# v5m.net
KiCad netlist of a schematic drawn in EAGLE
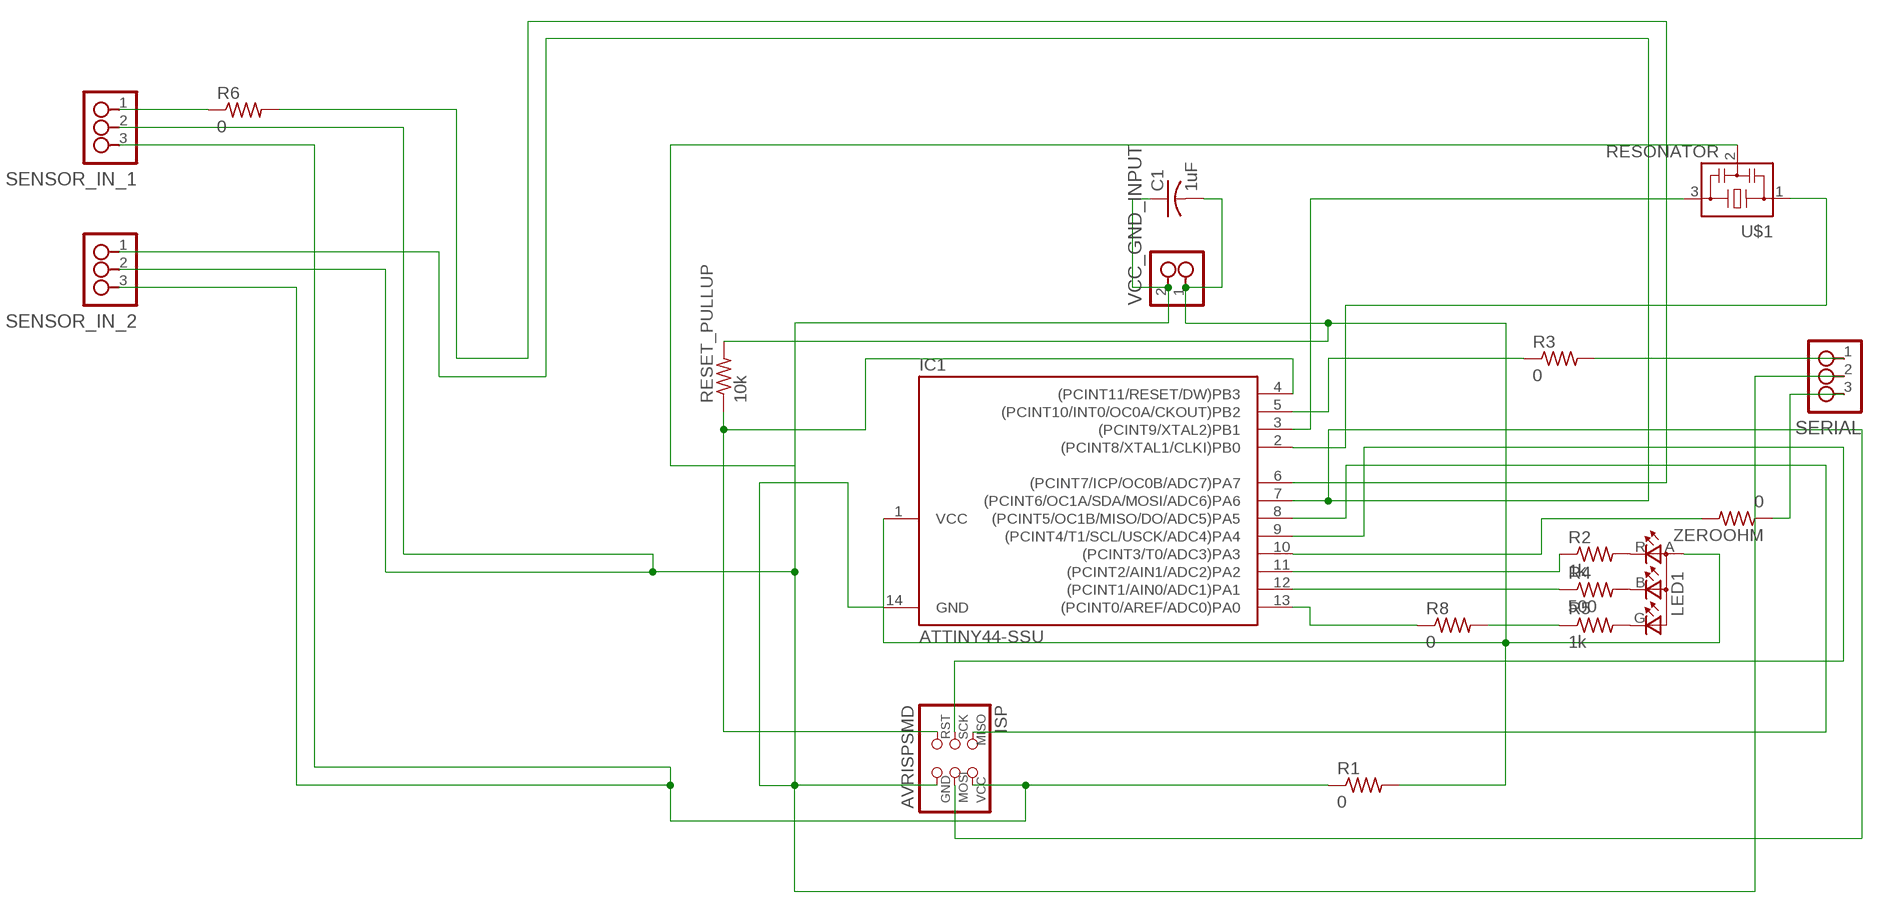
[diagram p0: schematic, sheet 1]

(export (version "E")
  (design (tool "Eeschema 10.0.6"))
  (components
    (comp (ref "C1")
      (value "1uF")
      (footprint "eagle-import:C1206")
      (libsource (lib "eagle-import") (part "C-USC1206"))
    )
    (comp (ref "IC1")
      (value "ATTINY44-SSU")
      (footprint "eagle-import:SOIC14")
      (libsource (lib "eagle-import") (part "ATTINY44-SSU"))
    )
    (comp (ref "ISP")
      (value "AVRISPSMD")
      (footprint "eagle-import:2X03SMD")
      (libsource (lib "eagle-import") (part "AVRISPSMD"))
    )
    (comp (ref "LED1")
      (value "LEDRGBOLD")
      (footprint "eagle-import:P-LCC-4-3")
      (libsource (lib "eagle-import") (part "LEDRGBOLD"))
    )
    (comp (ref "R1")
      (value "0")
      (footprint "eagle-import:R1206")
      (libsource (lib "eagle-import") (part "RES-US1206"))
    )
    (comp (ref "R2")
      (value "1k")
      (footprint "eagle-import:R1206")
      (libsource (lib "eagle-import") (part "RES-US1206"))
    )
    (comp (ref "R3")
      (value "0")
      (footprint "eagle-import:R1206")
      (libsource (lib "eagle-import") (part "RES-US1206"))
    )
    (comp (ref "R4")
      (value "500")
      (footprint "eagle-import:R1206")
      (libsource (lib "eagle-import") (part "RES-US1206"))
    )
    (comp (ref "R5")
      (value "1k")
      (footprint "eagle-import:R1206")
      (libsource (lib "eagle-import") (part "RES-US1206"))
    )
    (comp (ref "R6")
      (value "0")
      (footprint "eagle-import:R1206")
      (libsource (lib "eagle-import") (part "RES-US1206"))
    )
    (comp (ref "R8")
      (value "0")
      (footprint "eagle-import:R1206")
      (libsource (lib "eagle-import") (part "RES-US1206"))
    )
    (comp (ref "RESET_PULLUP")
      (value "10k")
      (footprint "eagle-import:R1206")
      (libsource (lib "eagle-import") (part "R-US_R1206"))
    )
    (comp (ref "SENSOR_IN_1")
      (value "3_PIN_HEADERHEADER")
      (footprint "eagle-import:SMT_PINS_3")
      (libsource (lib "eagle-import") (part "3_PIN_HEADERHEADER"))
    )
    (comp (ref "SENSOR_IN_2")
      (value "3_PIN_HEADERHEADER")
      (footprint "eagle-import:SMT_PINS_3")
      (libsource (lib "eagle-import") (part "3_PIN_HEADERHEADER"))
    )
    (comp (ref "SERIAL")
      (value "3_PIN_HEADERHEADER")
      (footprint "eagle-import:SMT_PINS_3")
      (libsource (lib "eagle-import") (part "3_PIN_HEADERHEADER"))
    )
    (comp (ref "U$1")
      (value "RESONATOR")
      (footprint "eagle-import:EFOBM")
      (libsource (lib "eagle-import") (part "RESONATOR"))
    )
    (comp (ref "VCC_GND_INPUT")
      (value "2_PIN_HEADERHEADER")
      (footprint "eagle-import:SMT_PINS_2")
      (libsource (lib "eagle-import") (part "2_PIN_HEADERHEADER"))
    )
    (comp (ref "ZEROOHM")
      (value "0")
      (footprint "eagle-import:R1206")
      (libsource (lib "eagle-import") (part "R-US_R1206"))
    )
  )
  (nets
    (net (code "1") (name "Net-(IC1-(PCINT0{slash}AREF{slash}ADC0)PA0)") (class "Default")
      (node (ref "IC1") (pin "13") (pinfunction "(PCINT0/AREF/ADC0)PA0_13") (pintype "bidirectional"))
      (node (ref "R8") (pin "1") (pinfunction "1_1") (pintype "passive"))
    )
    (net (code "2") (name "Net-(IC1-(PCINT1{slash}AIN0{slash}ADC1)PA1)") (class "Default")
      (node (ref "IC1") (pin "12") (pinfunction "(PCINT1/AIN0/ADC1)PA1_12") (pintype "bidirectional"))
      (node (ref "R4") (pin "1") (pinfunction "1_1") (pintype "passive"))
    )
    (net (code "3") (name "Net-(IC1-(PCINT2{slash}AIN1{slash}ADC2)PA2)") (class "Default")
      (node (ref "IC1") (pin "11") (pinfunction "(PCINT2/AIN1/ADC2)PA2_11") (pintype "bidirectional"))
      (node (ref "R2") (pin "1") (pinfunction "1_1") (pintype "passive"))
    )
    (net (code "4") (name "Net-(IC1-(PCINT3{slash}T0{slash}ADC3)PA3)") (class "Default")
      (node (ref "IC1") (pin "10") (pinfunction "(PCINT3/T0/ADC3)PA3_10") (pintype "bidirectional"))
      (node (ref "ZEROOHM") (pin "2") (pinfunction "2_2") (pintype "passive"))
    )
    (net (code "5") (name "Net-(IC1-(PCINT4{slash}T1{slash}SCL{slash}USCK{slash}ADC4)PA4)") (class "Default")
      (node (ref "IC1") (pin "9") (pinfunction "(PCINT4/T1/SCL/USCK/ADC4)PA4_9") (pintype "bidirectional"))
      (node (ref "ISP") (pin "3") (pinfunction "SCK_3") (pintype "passive"))
    )
    (net (code "6") (name "Net-(IC1-(PCINT5{slash}OC1B{slash}MISO{slash}DO{slash}ADC5)PA5)") (class "Default")
      (node (ref "IC1") (pin "8") (pinfunction "(PCINT5/OC1B/MISO/DO/ADC5)PA5_8") (pintype "bidirectional"))
      (node (ref "ISP") (pin "1") (pinfunction "MISO_1") (pintype "passive"))
    )
    (net (code "7") (name "Net-(IC1-(PCINT6{slash}OC1A{slash}SDA{slash}MOSI{slash}ADC6)PA6)") (class "Default")
      (node (ref "IC1") (pin "7") (pinfunction "(PCINT6/OC1A/SDA/MOSI/ADC6)PA6_7") (pintype "bidirectional"))
      (node (ref "ISP") (pin "4") (pinfunction "MOSI_4") (pintype "passive"))
      (node (ref "SENSOR_IN_2") (pin "1") (pinfunction "P$1_1") (pintype "bidirectional"))
    )
    (net (code "8") (name "Net-(IC1-(PCINT7{slash}ICP{slash}OC0B{slash}ADC7)PA7)") (class "Default")
      (node (ref "IC1") (pin "6") (pinfunction "(PCINT7/ICP/OC0B/ADC7)PA7_6") (pintype "bidirectional"))
      (node (ref "R6") (pin "2") (pinfunction "2_2") (pintype "passive"))
    )
    (net (code "9") (name "Net-(IC1-(PCINT8{slash}XTAL1{slash}CLKI)PB0)") (class "Default")
      (node (ref "IC1") (pin "2") (pinfunction "(PCINT8/XTAL1/CLKI)PB0_2") (pintype "bidirectional"))
      (node (ref "U$1") (pin "1") (pinfunction "1_1") (pintype "passive"))
    )
    (net (code "10") (name "Net-(IC1-(PCINT9{slash}XTAL2)PB1)") (class "Default")
      (node (ref "IC1") (pin "3") (pinfunction "(PCINT9/XTAL2)PB1_3") (pintype "bidirectional"))
      (node (ref "U$1") (pin "3") (pinfunction "3_3") (pintype "passive"))
    )
    (net (code "11") (name "Net-(IC1-(PCINT10{slash}INT0{slash}OC0A{slash}CKOUT)PB2)") (class "Default")
      (node (ref "IC1") (pin "5") (pinfunction "(PCINT10/INT0/OC0A/CKOUT)PB2_5") (pintype "bidirectional"))
      (node (ref "R3") (pin "1") (pinfunction "1_1") (pintype "passive"))
    )
    (net (code "12") (name "Net-(IC1-(PCINT11{slash}RESET{slash}DW)PB3)") (class "Default")
      (node (ref "IC1") (pin "4") (pinfunction "(PCINT11/RESET/DW)PB3_4") (pintype "bidirectional"))
      (node (ref "ISP") (pin "5") (pinfunction "RST_5") (pintype "passive"))
      (node (ref "RESET_PULLUP") (pin "1") (pinfunction "1_1") (pintype "passive"))
    )
    (net (code "13") (name "Net-(IC1-GND)") (class "Default")
      (node (ref "C1") (pin "1") (pinfunction "1_1") (pintype "passive"))
      (node (ref "IC1") (pin "14") (pinfunction "GND_14") (pintype "power_in"))
      (node (ref "ISP") (pin "6") (pinfunction "GND_6") (pintype "passive"))
      (node (ref "SENSOR_IN_1") (pin "2") (pinfunction "P$2_2") (pintype "bidirectional"))
      (node (ref "SENSOR_IN_2") (pin "2") (pinfunction "P$2_2") (pintype "bidirectional"))
      (node (ref "SERIAL") (pin "2") (pinfunction "P$2_2") (pintype "bidirectional"))
      (node (ref "U$1") (pin "2") (pinfunction "2_2") (pintype "passive"))
      (node (ref "VCC_GND_INPUT") (pin "2") (pinfunction "2_2") (pintype "bidirectional"))
    )
    (net (code "14") (name "Net-(IC1-VCC)") (class "Default")
      (node (ref "C1") (pin "2") (pinfunction "2_2") (pintype "passive"))
      (node (ref "IC1") (pin "1") (pinfunction "VCC_1") (pintype "power_in"))
      (node (ref "LED1") (pin "A") (pinfunction "A2_A") (pintype "passive"))
      (node (ref "R1") (pin "2") (pinfunction "2_2") (pintype "passive"))
      (node (ref "RESET_PULLUP") (pin "2") (pinfunction "2_2") (pintype "passive"))
      (node (ref "VCC_GND_INPUT") (pin "1") (pinfunction "1_1") (pintype "bidirectional"))
    )
    (net (code "15") (name "Net-(ISP-VCC)") (class "Default")
      (node (ref "ISP") (pin "2") (pinfunction "VCC_2") (pintype "passive"))
      (node (ref "R1") (pin "1") (pinfunction "1_1") (pintype "passive"))
      (node (ref "SENSOR_IN_1") (pin "3") (pinfunction "P$3_3") (pintype "bidirectional"))
      (node (ref "SENSOR_IN_2") (pin "3") (pinfunction "P$3_3") (pintype "bidirectional"))
    )
    (net (code "16") (name "Net-(LED1-CBLUE)") (class "Default")
      (node (ref "LED1") (pin "B") (pinfunction "CBLUE_B") (pintype "passive"))
      (node (ref "R4") (pin "2") (pinfunction "2_2") (pintype "passive"))
    )
    (net (code "17") (name "Net-(LED1-CGREEN)") (class "Default")
      (node (ref "LED1") (pin "G") (pinfunction "CGREEN_G") (pintype "passive"))
      (node (ref "R5") (pin "2") (pinfunction "2_2") (pintype "passive"))
    )
    (net (code "18") (name "Net-(LED1-CRED)") (class "Default")
      (node (ref "LED1") (pin "R") (pinfunction "CRED_R") (pintype "passive"))
      (node (ref "R2") (pin "2") (pinfunction "2_2") (pintype "passive"))
    )
    (net (code "19") (name "Net-(R5-Pad1)") (class "Default")
      (node (ref "R5") (pin "1") (pinfunction "1_1") (pintype "passive"))
      (node (ref "R8") (pin "2") (pinfunction "2_2") (pintype "passive"))
    )
    (net (code "20") (name "Net-(SENSOR_IN_1-P$1)") (class "Default")
      (node (ref "R6") (pin "1") (pinfunction "1_1") (pintype "passive"))
      (node (ref "SENSOR_IN_1") (pin "1") (pinfunction "P$1_1") (pintype "bidirectional"))
    )
    (net (code "21") (name "Net-(SERIAL-P$1)") (class "Default")
      (node (ref "R3") (pin "2") (pinfunction "2_2") (pintype "passive"))
      (node (ref "SERIAL") (pin "1") (pinfunction "P$1_1") (pintype "bidirectional"))
    )
    (net (code "22") (name "Net-(SERIAL-P$3)") (class "Default")
      (node (ref "SERIAL") (pin "3") (pinfunction "P$3_3") (pintype "bidirectional"))
      (node (ref "ZEROOHM") (pin "1") (pinfunction "1_1") (pintype "passive"))
    )
  )
)
